# partybooth.net
KiCad netlist of a schematic drawn in EAGLE
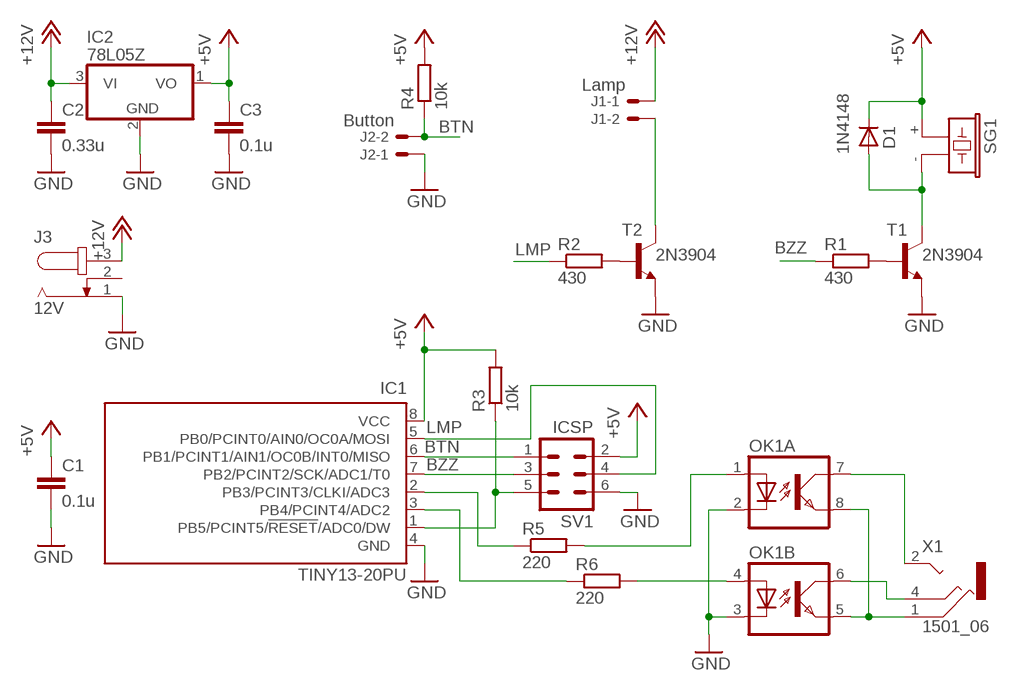
[diagram p0: schematic, sheet 1]

(export (version "E")
  (design (tool "Eeschema 10.0.6"))
  (components
    (comp (ref "C1")
      (value "0.1u")
      (footprint "eagle-import:C050-025X075")
      (libsource (lib "eagle-import") (part "C-EU050-025X075"))
    )
    (comp (ref "C2")
      (value "0.33u")
      (footprint "eagle-import:C050-025X075")
      (libsource (lib "eagle-import") (part "C-EU050-025X075"))
    )
    (comp (ref "C3")
      (value "0.1u")
      (footprint "eagle-import:C050-025X075")
      (libsource (lib "eagle-import") (part "C-EU050-025X075"))
    )
    (comp (ref "D1")
      (value "1N4148")
      (footprint "eagle-import:DO35-7")
      (libsource (lib "eagle-import") (part "1N4148DO35-7"))
    )
    (comp (ref "IC1")
      (value "TINY13-20PU")
      (footprint "eagle-import:DIL08")
      (fields (field (name "MPN") "ATTINY13-20PU"))
      (libsource (lib "eagle-import") (part "TINY13PU-20"))
    )
    (comp (ref "IC2")
      (value "78L05Z")
      (footprint "eagle-import:TO92")
      (libsource (lib "eagle-import") (part "78ZL05"))
    )
    (comp (ref "J1")
      (value "Lamp")
      (footprint "eagle-import:6410-02")
      (libsource (lib "eagle-import") (part "22-?-0227-2021"))
    )
    (comp (ref "J2")
      (value "Button")
      (footprint "eagle-import:6410-02")
      (libsource (lib "eagle-import") (part "22-?-0227-2021"))
    )
    (comp (ref "J3")
      (value "12V")
      (footprint "eagle-import:SPC4077")
      (libsource (lib "eagle-import") (part "JACK-PLUG0"))
    )
    (comp (ref "OK1")
      (value "ILD2")
      (footprint "eagle-import:DIL08")
      (libsource (lib "eagle-import") (part "ILD2"))
    )
    (comp (ref "R1")
      (value "430")
      (footprint "eagle-import:0204_7")
      (libsource (lib "eagle-import") (part "R-EU_0204/7"))
    )
    (comp (ref "R2")
      (value "430")
      (footprint "eagle-import:0204_7")
      (libsource (lib "eagle-import") (part "R-EU_0204/7"))
    )
    (comp (ref "R3")
      (value "10k")
      (footprint "eagle-import:0204_7")
      (libsource (lib "eagle-import") (part "R-EU_0204/7"))
    )
    (comp (ref "R4")
      (value "10k")
      (footprint "eagle-import:0204_7")
      (libsource (lib "eagle-import") (part "R-EU_0204/7"))
    )
    (comp (ref "R5")
      (value "220")
      (footprint "eagle-import:0204_7")
      (libsource (lib "eagle-import") (part "R-EU_0204/7"))
    )
    (comp (ref "R6")
      (value "220")
      (footprint "eagle-import:0204_7")
      (libsource (lib "eagle-import") (part "R-EU_0204/7"))
    )
    (comp (ref "SG1")
      (value "F/CM12P")
      (footprint "eagle-import:F_CM12P")
      (libsource (lib "eagle-import") (part "F/CM12P"))
    )
    (comp (ref "SV1")
      (value "ICSP")
      (footprint "eagle-import:MA03-2")
      (libsource (lib "eagle-import") (part "MA03-2"))
    )
    (comp (ref "T1")
      (value "2N3904")
      (footprint "eagle-import:TO92")
      (libsource (lib "eagle-import") (part "2N3904"))
    )
    (comp (ref "T2")
      (value "2N3904")
      (footprint "eagle-import:TO92")
      (libsource (lib "eagle-import") (part "2N3904"))
    )
    (comp (ref "X1")
      (value "1501_06")
      (footprint "eagle-import:1501_06")
      (libsource (lib "eagle-import") (part "1501_06"))
    )
  )
  (nets
    (net (code "1") (name "+5V") (class "Default")
      (node (ref "C1") (pin "1") (pinfunction "1_1") (pintype "passive"))
      (node (ref "C3") (pin "1") (pinfunction "1_1") (pintype "passive"))
      (node (ref "D1") (pin "C") (pinfunction "C_C") (pintype "passive"))
      (node (ref "IC1") (pin "8") (pinfunction "VCC_8") (pintype "power_in"))
      (node (ref "IC2") (pin "1") (pinfunction "VO_1") (pintype "passive"))
      (node (ref "R3") (pin "2") (pinfunction "2_2") (pintype "passive"))
      (node (ref "R4") (pin "2") (pinfunction "2_2") (pintype "passive"))
      (node (ref "SG1") (pin "+") (pinfunction "1_+") (pintype "passive"))
      (node (ref "SV1") (pin "2") (pinfunction "2_2") (pintype "passive"))
    )
    (net (code "2") (name "+12V") (class "Default")
      (node (ref "C2") (pin "1") (pinfunction "1_1") (pintype "passive"))
      (node (ref "IC2") (pin "3") (pinfunction "VI_3") (pintype "input"))
      (node (ref "J1") (pin "1") (pinfunction "S_1") (pintype "passive"))
      (node (ref "J3") (pin "3") (pinfunction "3_3") (pintype "passive"))
    )
    (net (code "3") (name "/BTN") (class "Default")
      (node (ref "IC1") (pin "6") (pinfunction "PB1/PCINT1/AIN1/OC0B/INT0/MISO_6") (pintype "bidirectional"))
      (node (ref "J2") (pin "2") (pinfunction "S_2") (pintype "passive"))
      (node (ref "R4") (pin "1") (pinfunction "1_1") (pintype "passive"))
      (node (ref "SV1") (pin "1") (pinfunction "1_1") (pintype "passive"))
    )
    (net (code "4") (name "/BZZ") (class "Default")
      (node (ref "IC1") (pin "7") (pinfunction "PB2/PCINT2/SCK/ADC1/T0_7") (pintype "bidirectional"))
      (node (ref "R1") (pin "1") (pinfunction "1_1") (pintype "passive"))
      (node (ref "SV1") (pin "3") (pinfunction "3_3") (pintype "passive"))
    )
    (net (code "5") (name "/LMP") (class "Default")
      (node (ref "IC1") (pin "5") (pinfunction "PB0/PCINT0/AIN0/OC0A/MOSI_5") (pintype "bidirectional"))
      (node (ref "R2") (pin "1") (pinfunction "1_1") (pintype "passive"))
      (node (ref "SV1") (pin "4") (pinfunction "4_4") (pintype "passive"))
    )
    (net (code "6") (name "GND") (class "Default")
      (node (ref "C1") (pin "2") (pinfunction "2_2") (pintype "passive"))
      (node (ref "C2") (pin "2") (pinfunction "2_2") (pintype "passive"))
      (node (ref "C3") (pin "2") (pinfunction "2_2") (pintype "passive"))
      (node (ref "IC1") (pin "4") (pinfunction "GND_4") (pintype "power_in"))
      (node (ref "IC2") (pin "2") (pinfunction "GND_2") (pintype "passive"))
      (node (ref "J2") (pin "1") (pinfunction "S_1") (pintype "passive"))
      (node (ref "J3") (pin "1") (pinfunction "1_1") (pintype "passive"))
      (node (ref "OK1") (pin "2") (pinfunction "C_2") (pintype "passive"))
      (node (ref "OK1") (pin "3") (pinfunction "C_3") (pintype "passive"))
      (node (ref "SV1") (pin "6") (pinfunction "6_6") (pintype "passive"))
      (node (ref "T1") (pin "3") (pinfunction "E_3") (pintype "passive"))
      (node (ref "T2") (pin "3") (pinfunction "E_3") (pintype "passive"))
    )
    (net (code "7") (name "Net-(IC1-PB3{slash}PCINT3{slash}CLKI{slash}ADC3)") (class "Default")
      (node (ref "IC1") (pin "2") (pinfunction "PB3/PCINT3/CLKI/ADC3_2") (pintype "bidirectional"))
      (node (ref "R5") (pin "1") (pinfunction "1_1") (pintype "passive"))
    )
    (net (code "8") (name "Net-(IC1-PB4{slash}PCINT4{slash}ADC2)") (class "Default")
      (node (ref "IC1") (pin "3") (pinfunction "PB4/PCINT4/ADC2_3") (pintype "bidirectional"))
      (node (ref "R6") (pin "1") (pinfunction "1_1") (pintype "passive"))
    )
    (net (code "9") (name "Net-(IC1-PB5{slash}PCINT5{slash}~{RESET}{slash}ADC0{slash}DW)") (class "Default")
      (node (ref "IC1") (pin "1") (pinfunction "PB5/PCINT5/~{RESET}/ADC0/DW_1") (pintype "bidirectional"))
      (node (ref "R3") (pin "1") (pinfunction "1_1") (pintype "passive"))
      (node (ref "SV1") (pin "5") (pinfunction "5_5") (pintype "passive"))
    )
    (net (code "10") (name "Net-(J1B-S)") (class "Default")
      (node (ref "J1") (pin "2") (pinfunction "S_2") (pintype "passive"))
      (node (ref "T2") (pin "1") (pinfunction "C_1") (pintype "passive"))
    )
    (net (code "11") (name "Net-(OK1A-A)") (class "Default")
      (node (ref "OK1") (pin "1") (pinfunction "A_1") (pintype "passive"))
      (node (ref "R5") (pin "2") (pinfunction "2_2") (pintype "passive"))
    )
    (net (code "12") (name "Net-(OK1A-COL)") (class "Default")
      (node (ref "OK1") (pin "7") (pinfunction "COL_7") (pintype "passive"))
      (node (ref "X1") (pin "2") (pinfunction "2_2") (pintype "passive"))
    )
    (net (code "13") (name "Net-(OK1A-EMIT)") (class "Default")
      (node (ref "OK1") (pin "5") (pinfunction "EMIT_5") (pintype "passive"))
      (node (ref "OK1") (pin "8") (pinfunction "EMIT_8") (pintype "passive"))
      (node (ref "X1") (pin "1") (pinfunction "1_1") (pintype "passive"))
    )
    (net (code "14") (name "Net-(OK1B-A)") (class "Default")
      (node (ref "OK1") (pin "4") (pinfunction "A_4") (pintype "passive"))
      (node (ref "R6") (pin "2") (pinfunction "2_2") (pintype "passive"))
    )
    (net (code "15") (name "Net-(OK1B-COL)") (class "Default")
      (node (ref "OK1") (pin "6") (pinfunction "COL_6") (pintype "passive"))
      (node (ref "X1") (pin "4") (pinfunction "3_4") (pintype "passive"))
    )
    (net (code "16") (name "Net-(SG1-2)") (class "Default")
      (node (ref "D1") (pin "A") (pinfunction "A_A") (pintype "passive"))
      (node (ref "SG1") (pin "-") (pinfunction "2_-") (pintype "passive"))
      (node (ref "T1") (pin "1") (pinfunction "C_1") (pintype "passive"))
    )
    (net (code "17") (name "Net-(T1-B)") (class "Default")
      (node (ref "R1") (pin "2") (pinfunction "2_2") (pintype "passive"))
      (node (ref "T1") (pin "2") (pinfunction "B_2") (pintype "passive"))
    )
    (net (code "18") (name "Net-(T2-B)") (class "Default")
      (node (ref "R2") (pin "2") (pinfunction "2_2") (pintype "passive"))
      (node (ref "T2") (pin "2") (pinfunction "B_2") (pintype "passive"))
    )
    (net (code "19") (name "unconnected-(J3-Pad2)") (class "Default")
      (node (ref "J3") (pin "2") (pinfunction "2_2") (pintype "passive"))
    )
  )
)
